# Leptons_Voltmeter.net
KiCad netlist of a schematic drawn in Altium Designer
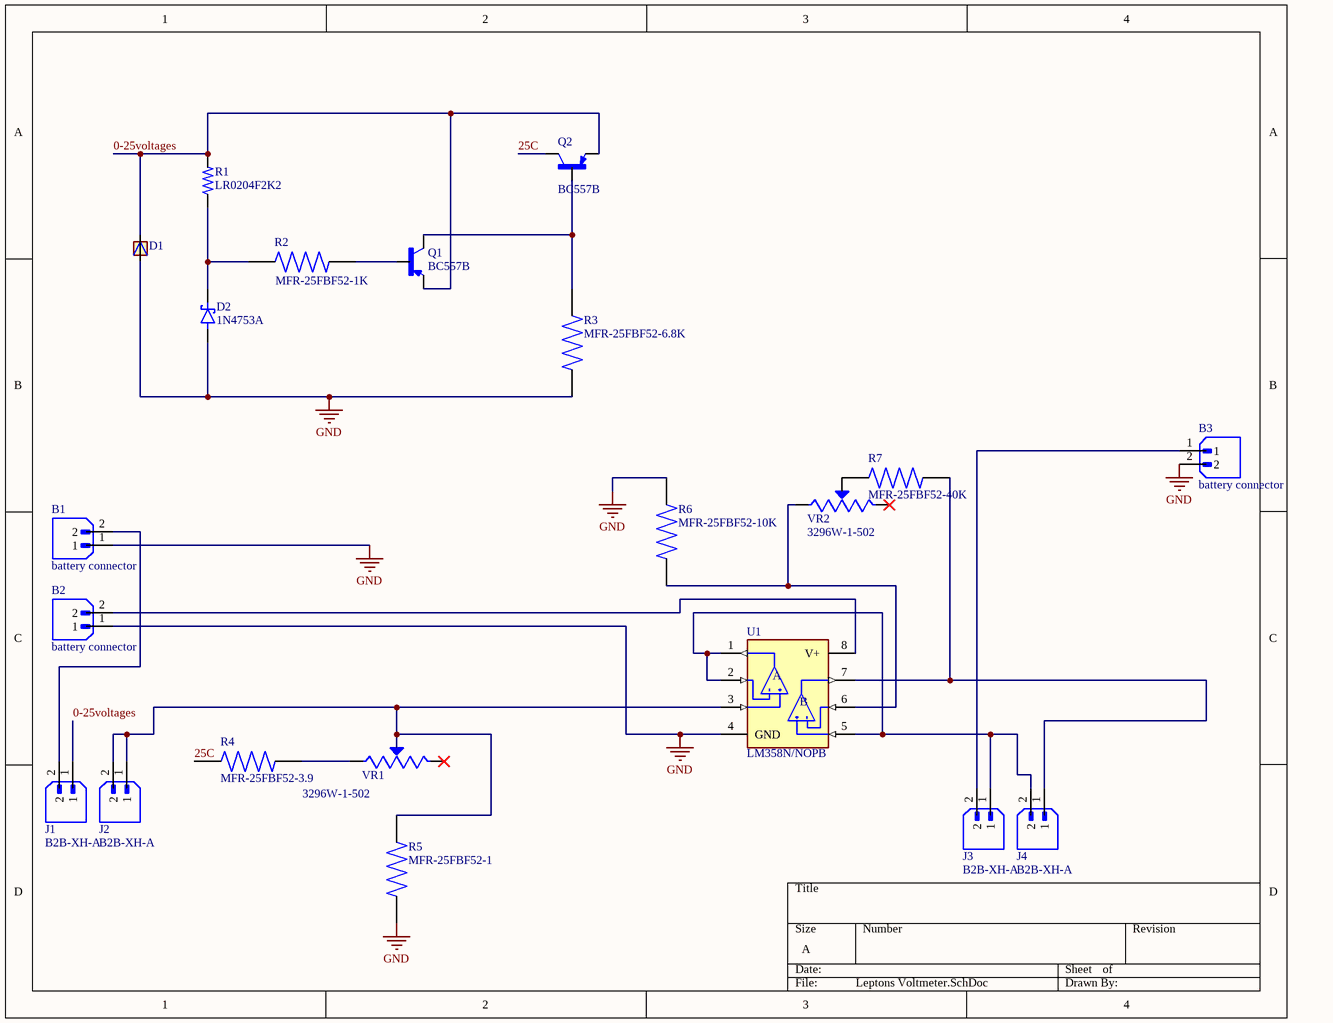
[diagram p0: Leptons Voltmeter.SchDoc]

(export (version "E")
  (design (tool "Eeschema 10.0.6"))
  (components
    (comp (ref "B1")
      (value "battery connector")
      (footprint "JST_B2B-XH-A(LF)(SN)")
      (libsource (lib "") (part "battery connector_1"))
    )
    (comp (ref "B2")
      (value "battery connector")
      (footprint "JST_B2B-XH-A(LF)(SN)")
      (libsource (lib "") (part "battery connector_1"))
    )
    (comp (ref "B3")
      (value "battery connector")
      (footprint "JST_B2B-XH-A(LF)(SN)")
      (libsource (lib "edp") (part "battery connector"))
    )
    (comp (ref "D1")
      (value "1N4004G")
      (footprint "DO41-10")
      (description "Diode Standard 400 V 1A Through Hole DO-41")
      (fields (field (name "MF") "Diodes Inc.") (field (name "MP") "1N4004G-T"))
      (libsource (lib "1N4004G") (part "1N4004G"))
    )
    (comp (ref "D2")
      (value "1N4753A")
      (footprint "DIOAD1036W78L463D272")
      (description "Zener Diode Single 36V 5% 50Ohm 1000mW 2-Pin")
      (fields (field (name "MF") "ON Semiconductor"))
      (libsource (lib "1N4753A") (part "1N4753A"))
    )
    (comp (ref "J1")
      (value "B2B-XH-A")
      (footprint "JST_B2B-XH-A")
      (fields (field (name "MF") "{'manufacturer': u'JST Sales America Inc.'}"))
      (libsource (lib "B2B-XH-A") (part "B2B-XH-A"))
    )
    (comp (ref "J2")
      (value "B2B-XH-A")
      (footprint "JST_B2B-XH-A")
      (fields (field (name "MF") "{'manufacturer': u'JST Sales America Inc.'}"))
      (libsource (lib "B2B-XH-A") (part "B2B-XH-A"))
    )
    (comp (ref "J3")
      (value "B2B-XH-A")
      (footprint "JST_B2B-XH-A")
      (fields (field (name "MF") "{'manufacturer': u'JST Sales America Inc.'}"))
      (libsource (lib "B2B-XH-A") (part "B2B-XH-A"))
    )
    (comp (ref "J4")
      (value "B2B-XH-A")
      (footprint "JST_B2B-XH-A")
      (fields (field (name "MF") "{'manufacturer': u'JST Sales America Inc.'}"))
      (libsource (lib "B2B-XH-A") (part "B2B-XH-A"))
    )
    (comp (ref "Q1")
      (value "BC557B")
      (footprint "TO92254P460H750-3")
      (description "Bipolar (BJT) Transistor PNP 45 V 100 mA 320MHz 625 mW Through Hole TO-92 (TO-226)")
      (fields (field (name "MF") "ON Semiconductor"))
      (libsource (lib "BC557B") (part "BC557B"))
    )
    (comp (ref "Q2")
      (value "BC557B")
      (footprint "TO92254P460H750-3")
      (description "Bipolar (BJT) Transistor PNP 45 V 100 mA 320MHz 625 mW Through Hole TO-92 (TO-226)")
      (fields (field (name "MF") "ON Semiconductor"))
      (libsource (lib "") (part "BC557B_1"))
    )
    (comp (ref "R1")
      (value "LR0204F2K2")
      (footprint "RESAD640W45L370D200")
      (description "2.2 kOhms Â±1% 0.25W, 1/4W Through Hole Resistor Axial - Metal Film")
      (fields (field (name "MF") "TE Connectivity Passive Product"))
      (libsource (lib "LR0204F2K2") (part "LR0204F2K2"))
    )
    (comp (ref "R2")
      (value "MFR-25FBF52-1K")
      (footprint "RESAD1100W55L680D260")
      (description "1.07 kOhms Â±1% 0.25W, 1/4W Through Hole Resistor Axial - Metal Film")
      (fields (field (name "MF") "Yageo"))
      (libsource (lib "MFR-25FBF52-1K") (part "MFR-25FBF52-1K"))
    )
    (comp (ref "R3")
      (value "MFR-25FBF52-6.8K")
      (footprint "RESAD1100W55L680D260")
      (description "1.07 kOhms Â±1% 0.25W, 1/4W Through Hole Resistor Axial - Metal Film")
      (fields (field (name "MF") "Yageo") (field (name "MP") "MFR-25FBF52-1K"))
      (libsource (lib "MFR-25FBF52-1K") (part "MFR-25FBF52-1K"))
    )
    (comp (ref "R4")
      (value "MFR-25FBF52-3.9")
      (footprint "RESAD1100W55L680D260")
      (description "1.07 kOhms Â±1% 0.25W, 1/4W Through Hole Resistor Axial - Metal Film")
      (fields (field (name "MF") "Yageo") (field (name "MP") "MFR-25FBF52-1K"))
      (libsource (lib "MFR-25FBF52-1K") (part "MFR-25FBF52-1K"))
    )
    (comp (ref "R5")
      (value "MFR-25FBF52-1")
      (footprint "RESAD1100W55L680D260")
      (description "1.07 kOhms Â±1% 0.25W, 1/4W Through Hole Resistor Axial - Metal Film")
      (fields (field (name "MF") "Yageo") (field (name "MP") "MFR-25FBF52-1K"))
      (libsource (lib "MFR-25FBF52-1K") (part "MFR-25FBF52-1K"))
    )
    (comp (ref "R6")
      (value "MFR-25FBF52-10K")
      (footprint "RESAD1100W55L680D260")
      (description "1.07 kOhms Â±1% 0.25W, 1/4W Through Hole Resistor Axial - Metal Film")
      (fields (field (name "MF") "Yageo") (field (name "MP") "MFR-25FBF52-1K"))
      (libsource (lib "MFR-25FBF52-1K") (part "MFR-25FBF52-1K"))
    )
    (comp (ref "R7")
      (value "MFR-25FBF52-40K")
      (footprint "RESAD1100W55L680D260")
      (description "1.07 kOhms Â±1% 0.25W, 1/4W Through Hole Resistor Axial - Metal Film")
      (fields (field (name "MF") "Yageo") (field (name "MP") "MFR-25FBF52-1K"))
      (libsource (lib "MFR-25FBF52-1K") (part "MFR-25FBF52-1K"))
    )
    (comp (ref "U1")
      (value "LM358N/NOPB")
      (footprint "DIP794W45P254L959H508Q8")
      (description "Dual, 32-V, 1-MHz op amp")
      (fields (field (name "MF") "Texas Instruments"))
      (libsource (lib "LM358N_NOPB") (part "LM358N/NOPB"))
    )
    (comp (ref "VR1")
      (value "3296W-1-502")
      (footprint "TRIM_3296W-1-502")
      (description "NON-RoHS, 3/8 Sq, Thru-Hole, TRIMMER, 5 Kohms, Cermet, 25 Turns, Pwr-Rtg 0.5W ¦ Bourns 3296W-1-502")
      (fields (field (name "MF") "Bourns"))
      (libsource (lib "3296W-1-502") (part "3296W-1-502"))
    )
    (comp (ref "VR2")
      (value "3296W-1-502")
      (footprint "TRIM_3296W-1-502")
      (description "NON-RoHS, 3/8 Sq, Thru-Hole, TRIMMER, 5 Kohms, Cermet, 25 Turns, Pwr-Rtg 0.5W ¦ Bourns 3296W-1-502")
      (fields (field (name "MF") "Bourns"))
      (libsource (lib "3296W-1-502") (part "3296W-1-502"))
    )
  )
  (nets
    (net (code "1") (name "/0-25voltages") (class "Default")
      (node (ref "D1") (pin "C") (pinfunction "C_C") (pintype "passive"))
      (node (ref "J1") (pin "1") (pinfunction "1_1") (pintype "passive"))
      (node (ref "Q1") (pin "3") (pinfunction "E_3") (pintype "passive"))
      (node (ref "Q2") (pin "3") (pinfunction "E_3") (pintype "passive"))
      (node (ref "R1") (pin "2") (pinfunction "2_2") (pintype "passive"))
    )
    (net (code "2") (name "/25C") (class "Default")
      (node (ref "Q2") (pin "1") (pinfunction "C_1") (pintype "passive"))
      (node (ref "R4") (pin "1") (pinfunction "1_1") (pintype "passive"))
    )
    (net (code "3") (name "GND") (class "Default")
      (node (ref "B1") (pin "1") (pinfunction "1_1") (pintype "passive"))
      (node (ref "B2") (pin "1") (pinfunction "1_1") (pintype "passive"))
      (node (ref "B3") (pin "2") (pinfunction "2_2") (pintype "passive"))
      (node (ref "D1") (pin "A") (pinfunction "A_A") (pintype "passive"))
      (node (ref "D2") (pin "2") (pinfunction "A_2") (pintype "passive"))
      (node (ref "R3") (pin "2") (pinfunction "2_2") (pintype "passive"))
      (node (ref "R5") (pin "1") (pinfunction "1_1") (pintype "passive"))
      (node (ref "R6") (pin "2") (pinfunction "2_2") (pintype "passive"))
      (node (ref "U1") (pin "4") (pinfunction "GND_4") (pintype "power_in"))
    )
    (net (code "4") (name "Net-(B1-Pad2)") (class "Default")
      (node (ref "B1") (pin "2") (pinfunction "2_2") (pintype "passive"))
      (node (ref "J1") (pin "2") (pinfunction "2_2") (pintype "passive"))
    )
    (net (code "5") (name "Net-(B3-Pad1)") (class "Default")
      (node (ref "B3") (pin "1") (pinfunction "1_1") (pintype "passive"))
      (node (ref "J3") (pin "2") (pinfunction "2_2") (pintype "passive"))
    )
    (net (code "6") (name "Net-(D2-K)") (class "Default")
      (node (ref "D2") (pin "1") (pinfunction "K_1") (pintype "passive"))
      (node (ref "R1") (pin "1") (pinfunction "1_1") (pintype "passive"))
      (node (ref "R2") (pin "1") (pinfunction "1_1") (pintype "passive"))
    )
    (net (code "7") (name "Net-(Q1-B)") (class "Default")
      (node (ref "Q1") (pin "2") (pinfunction "B_2") (pintype "passive"))
      (node (ref "R2") (pin "2") (pinfunction "2_2") (pintype "passive"))
    )
    (net (code "8") (name "Net-(Q1-C)") (class "Default")
      (node (ref "Q1") (pin "1") (pinfunction "C_1") (pintype "passive"))
      (node (ref "Q2") (pin "2") (pinfunction "B_2") (pintype "passive"))
      (node (ref "R3") (pin "1") (pinfunction "1_1") (pintype "passive"))
    )
    (net (code "9") (name "Net-(U1-+INA)") (class "Default")
      (node (ref "J2") (pin "1") (pinfunction "1_1") (pintype "passive"))
      (node (ref "J2") (pin "2") (pinfunction "2_2") (pintype "passive"))
      (node (ref "R5") (pin "2") (pinfunction "2_2") (pintype "passive"))
      (node (ref "U1") (pin "3") (pinfunction "+INA_3") (pintype "input"))
      (node (ref "VR1") (pin "2") (pinfunction "WIPER_2") (pintype "passive"))
    )
    (net (code "10") (name "Net-(U1-+INB)") (class "Default")
      (node (ref "J3") (pin "1") (pinfunction "1_1") (pintype "passive"))
      (node (ref "J4") (pin "2") (pinfunction "2_2") (pintype "passive"))
      (node (ref "U1") (pin "1") (pinfunction "OUTA_1") (pintype "output"))
      (node (ref "U1") (pin "2") (pinfunction "-INA_2") (pintype "input"))
      (node (ref "U1") (pin "5") (pinfunction "+INB_5") (pintype "input"))
    )
    (net (code "11") (name "Net-(U1--INB)") (class "Default")
      (node (ref "R6") (pin "1") (pinfunction "1_1") (pintype "passive"))
      (node (ref "U1") (pin "6") (pinfunction "-INB_6") (pintype "input"))
      (node (ref "VR2") (pin "1") (pinfunction "CCW_1") (pintype "passive"))
    )
    (net (code "12") (name "Net-(U1-OUTB)") (class "Default")
      (node (ref "J4") (pin "1") (pinfunction "1_1") (pintype "passive"))
      (node (ref "R7") (pin "2") (pinfunction "2_2") (pintype "passive"))
      (node (ref "U1") (pin "7") (pinfunction "OUTB_7") (pintype "output"))
    )
    (net (code "13") (name "Net-(U1-V+)") (class "Default")
      (node (ref "B2") (pin "2") (pinfunction "2_2") (pintype "passive"))
      (node (ref "U1") (pin "8") (pinfunction "V+_8") (pintype "power_in"))
    )
    (net (code "14") (name "Net-(VR1-CCW)") (class "Default")
      (node (ref "R4") (pin "2") (pinfunction "2_2") (pintype "passive"))
      (node (ref "VR1") (pin "1") (pinfunction "CCW_1") (pintype "passive"))
    )
    (net (code "15") (name "Net-(VR2-WIPER)") (class "Default")
      (node (ref "R7") (pin "1") (pinfunction "1_1") (pintype "passive"))
      (node (ref "VR2") (pin "2") (pinfunction "WIPER_2") (pintype "passive"))
    )
    (net (code "16") (name "unconnected-(VR1-CW-Pad3)") (class "Default")
      (node (ref "VR1") (pin "3") (pinfunction "CW_3") (pintype "passive+no_connect"))
    )
    (net (code "17") (name "unconnected-(VR2-CW-Pad3)") (class "Default")
      (node (ref "VR2") (pin "3") (pinfunction "CW_3") (pintype "passive+no_connect"))
    )
  )
)
